# PROC051C_XDS110_Interface_1A.net
KiCad netlist of a schematic drawn in Altium Designer
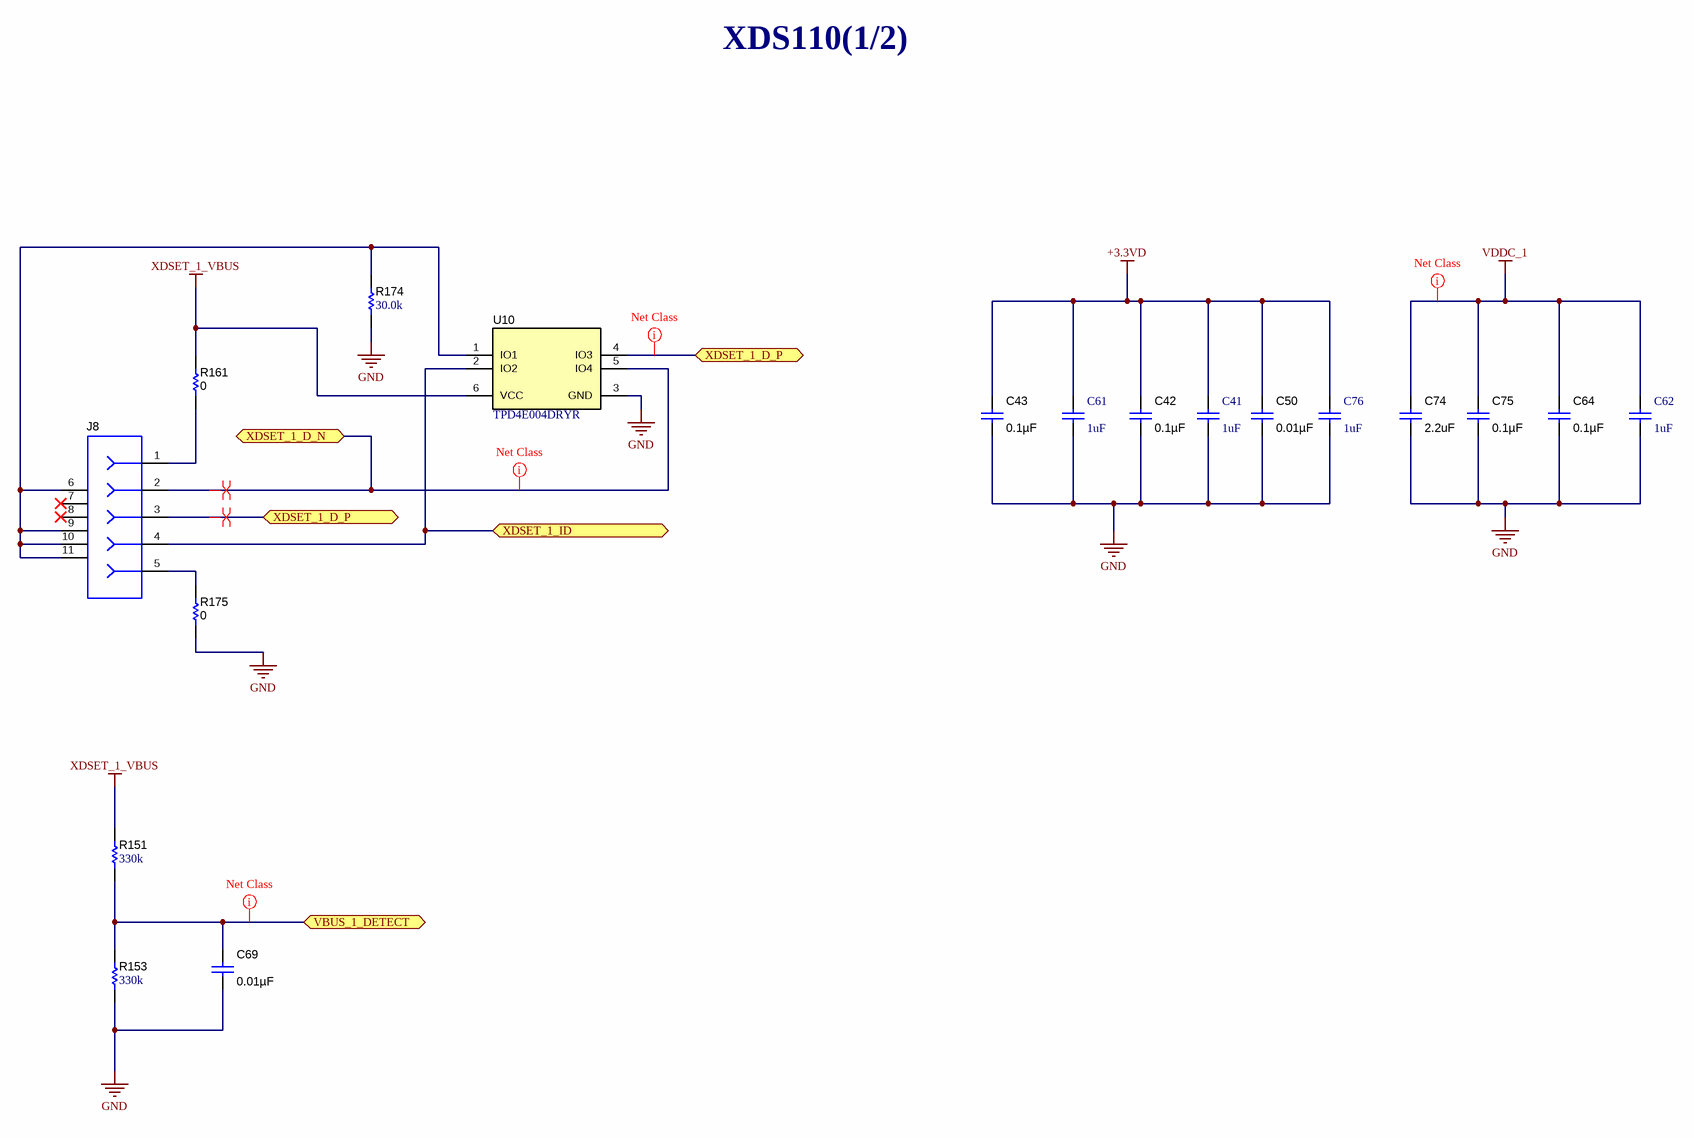
[diagram p0: PROC051C_XDS110 Interface_1A.SchDoc]

(export (version "E")
  (design (tool "Eeschema 10.0.6"))
  (components
    (comp (ref "C41")
      (value "GCM155C71A105KE38D")
      (footprint "0402_070")
      (description "CAP, CERM, 1 uF, 10 V, +/- 10%, X7S, AEC-Q200 Grade 1, 0402")
      (fields
        (field (name "MANUFACTURER") "MuRata")
        (field (name "VALUEDISPLAYED") "1uF")
        (field (name "PUBLISHER") "Texas Instruments")
      )
      (libsource (lib "Altium Vault - TI") (part "CMP-0006349-2"))
    )
    (comp (ref "C42")
      (value "C0402C104K8RACTU")
      (footprint "0402L")
      (description "CAP, CERM, 0.1 µF, 10 V,+/- 10%, X7R, 0402")
      (fields (field (name "MANUFACTURER") "Kemet") (field (name "VALUEDISPLAYED") "0.1µF"))
      (libsource (lib "Altium Vault - TI") (part "Capacitor"))
    )
    (comp (ref "C43")
      (value "C0402C104K8RACTU")
      (footprint "0402L")
      (description "CAP, CERM, 0.1 µF, 10 V,+/- 10%, X7R, 0402")
      (fields (field (name "MANUFACTURER") "Kemet") (field (name "VALUEDISPLAYED") "0.1µF"))
      (libsource (lib "Altium Vault - TI") (part "Capacitor"))
    )
    (comp (ref "C50")
      (value "C0402C103K4RACTU")
      (footprint "0402L")
      (description "CAP, CERM, 0.01 µF, 16 V,+/- 10%, X7R, 0402")
      (fields (field (name "MANUFACTURER") "Kemet") (field (name "VALUEDISPLAYED") "0.01µF"))
      (libsource (lib "Altium Vault - TI") (part "Capacitor"))
    )
    (comp (ref "C61")
      (value "GCM155C71A105KE38D")
      (footprint "0402_070")
      (description "CAP, CERM, 1 uF, 10 V, +/- 10%, X7S, AEC-Q200 Grade 1, 0402")
      (fields
        (field (name "MANUFACTURER") "MuRata")
        (field (name "VALUEDISPLAYED") "1uF")
        (field (name "PUBLISHER") "Texas Instruments")
      )
      (libsource (lib "Altium Vault - TI") (part "CMP-0006349-2"))
    )
    (comp (ref "C62")
      (value "GCM155C71A105KE38D")
      (footprint "0402_070")
      (description "CAP, CERM, 1 uF, 10 V, +/- 10%, X7S, AEC-Q200 Grade 1, 0402")
      (fields
        (field (name "MANUFACTURER") "MuRata")
        (field (name "VALUEDISPLAYED") "1uF")
        (field (name "PUBLISHER") "Texas Instruments")
      )
      (libsource (lib "Altium Vault - TI") (part "CMP-0006349-2"))
    )
    (comp (ref "C64")
      (value "C0402C104K8RACTU")
      (footprint "0402L")
      (description "CAP, CERM, 0.1 µF, 10 V,+/- 10%, X7R, 0402")
      (fields (field (name "MANUFACTURER") "Kemet") (field (name "VALUEDISPLAYED") "0.1µF"))
      (libsource (lib "Altium Vault - TI") (part "Capacitor"))
    )
    (comp (ref "C69")
      (value "C0402C103K4RACTU")
      (footprint "0402L")
      (description "CAP, CERM, 0.01 µF, 16 V,+/- 10%, X7R, 0402")
      (fields (field (name "MANUFACTURER") "Kemet") (field (name "VALUEDISPLAYED") "0.01µF"))
      (libsource (lib "Altium Vault - TI") (part "Capacitor"))
    )
    (comp (ref "C74")
      (value "C1005X7S1A225K050BC")
      (footprint "0402_065L")
      (description "CAP, CERM, 2.2 uF, 10 V, +/- 10%, X7S, 0402")
      (fields
        (field (name "MANUFACTURER") "TDK")
        (field (name "VALUEDISPLAYED") "2.2uF")
        (field (name "PUBLISHER") "Texas Instruments")
      )
      (libsource (lib "Altium Vault - TI") (part "CMP-0006302-2"))
    )
    (comp (ref "C75")
      (value "C0402C104K8RACTU")
      (footprint "0402L")
      (description "CAP, CERM, 0.1 µF, 10 V,+/- 10%, X7R, 0402")
      (fields (field (name "MANUFACTURER") "Kemet") (field (name "VALUEDISPLAYED") "0.1µF"))
      (libsource (lib "Altium Vault - TI") (part "Capacitor"))
    )
    (comp (ref "C76")
      (value "GCM155C71A105KE38D")
      (footprint "0402_070")
      (description "CAP, CERM, 1 uF, 10 V, +/- 10%, X7S, AEC-Q200 Grade 1, 0402")
      (fields
        (field (name "MANUFACTURER") "MuRata")
        (field (name "VALUEDISPLAYED") "1uF")
        (field (name "PUBLISHER") "Texas Instruments")
      )
      (libsource (lib "Altium Vault - TI") (part "CMP-0006349-2"))
    )
    (comp (ref "J8")
      (value "105017-0001")
      (footprint "CONN_105017-0001")
      (description "Connector, Receptacle, Micro-USB Type B, R/A, Bottom Mount SMT")
      (fields (field (name "MANUFACTURER") "Molex") (field (name "PUBLISHER") "Texas Instruments"))
      (libsource (lib "Altium Vault - TI") (part "CONN_105017-0001"))
    )
    (comp (ref "R151")
      (value "CRCW0402330KFKED")
      (footprint "0402L")
      (description "RES, 330 k, 1%, 0.063 W, AEC-Q200 Grade 0, 0402")
      (fields (field (name "MANUFACTURER") "Vishay-Dale") (field (name "VALUEDISPLAYED") "330k"))
      (libsource (lib "Altium Vault - TI") (part "Resistor"))
    )
    (comp (ref "R153")
      (value "CRCW0402330KFKED")
      (footprint "0402L")
      (description "RES, 330 k, 1%, 0.063 W, AEC-Q200 Grade 0, 0402")
      (fields (field (name "MANUFACTURER") "Vishay-Dale") (field (name "VALUEDISPLAYED") "330k"))
      (libsource (lib "Altium Vault - TI") (part "Resistor"))
    )
    (comp (ref "R161")
      (value "MCT06030Z0000ZP500")
      (footprint "0603")
      (description "RES, 0, 5%, 0.125 W, 0603")
      (fields
        (field (name "MANUFACTURER") "Vishay/Beyschlag")
        (field (name "VALUEDISPLAYED") "0")
        (field (name "PUBLISHER") "Texas Instruments")
      )
      (libsource (lib "Altium Vault - TI") (part "Resistor"))
    )
    (comp (ref "R174")
      (value "CRCW040230K0FKED")
      (footprint "0402L")
      (description "RES, 30.0 k, 1%, 0.063 W, AEC-Q200 Grade 0, 0402")
      (fields (field (name "MANUFACTURER") "Vishay-Dale") (field (name "VALUEDISPLAYED") "30.0k"))
      (libsource (lib "Altium Vault - TI") (part "Resistor"))
    )
    (comp (ref "R175")
      (value "MCT06030Z0000ZP500")
      (footprint "0603")
      (description "RES, 0, 5%, 0.125 W, 0603")
      (fields
        (field (name "MANUFACTURER") "Vishay/Beyschlag")
        (field (name "VALUEDISPLAYED") "0")
        (field (name "PUBLISHER") "Texas Instruments")
      )
      (libsource (lib "Altium Vault - TI") (part "Resistor"))
    )
    (comp (ref "U10")
      (value "TPD4E004DRYR")
      (footprint "DRY0006A")
      (description "4-Channel ESD Protection Array for High-Speed Data Interfaces, DRY0006A (USON-6)")
      (fields (field (name "MANUFACTURER") "Texas Instruments") (field (name "PARTNUMBER") "TPD4E004DRYR"))
      (libsource (lib "Altium Vault - TI") (part "TI-TPD4E004-SON_DRY-6"))
    )
  )
  (nets
    (net (code "1") (name "+3.3VD") (class "Default")
      (node (ref "C41") (pin "1") (pinfunction "1_1") (pintype "passive"))
      (node (ref "C42") (pin "2") (pinfunction "2_2") (pintype "passive"))
      (node (ref "C43") (pin "2") (pinfunction "2_2") (pintype "passive"))
      (node (ref "C50") (pin "2") (pinfunction "2_2") (pintype "passive"))
      (node (ref "C61") (pin "1") (pinfunction "1_1") (pintype "passive"))
      (node (ref "C76") (pin "1") (pinfunction "1_1") (pintype "passive"))
    )
    (net (code "2") (name "/VBUS_1_DETECT") (class "Default")
      (node (ref "C69") (pin "2") (pinfunction "2_2") (pintype "passive"))
      (node (ref "R151") (pin "1") (pinfunction "1_1") (pintype "passive"))
      (node (ref "R153") (pin "2") (pinfunction "2_2") (pintype "passive"))
    )
    (net (code "3") (name "/XDSET_1_D_N") (class "Default")
      (node (ref "J8") (pin "2") (pintype "passive"))
      (node (ref "U10") (pin "5") (pinfunction "IO4_5") (pintype "passive"))
    )
    (net (code "4") (name "/XDSET_1_D_P") (class "Default")
      (node (ref "J8") (pin "3") (pintype "passive"))
      (node (ref "U10") (pin "4") (pinfunction "IO3_4") (pintype "passive"))
    )
    (net (code "5") (name "/XDSET_1_ID") (class "Default")
      (node (ref "J8") (pin "4") (pintype "passive"))
      (node (ref "U10") (pin "2") (pinfunction "IO2_2") (pintype "passive"))
    )
    (net (code "6") (name "GND") (class "Default")
      (node (ref "C41") (pin "2") (pinfunction "2_2") (pintype "passive"))
      (node (ref "C42") (pin "1") (pinfunction "1_1") (pintype "passive"))
      (node (ref "C43") (pin "1") (pinfunction "1_1") (pintype "passive"))
      (node (ref "C50") (pin "1") (pinfunction "1_1") (pintype "passive"))
      (node (ref "C61") (pin "2") (pinfunction "2_2") (pintype "passive"))
      (node (ref "C62") (pin "2") (pinfunction "2_2") (pintype "passive"))
      (node (ref "C64") (pin "1") (pinfunction "1_1") (pintype "passive"))
      (node (ref "C69") (pin "1") (pinfunction "1_1") (pintype "passive"))
      (node (ref "C74") (pin "1") (pinfunction "1_1") (pintype "passive"))
      (node (ref "C75") (pin "1") (pinfunction "1_1") (pintype "passive"))
      (node (ref "C76") (pin "2") (pinfunction "2_2") (pintype "passive"))
      (node (ref "R153") (pin "1") (pinfunction "1_1") (pintype "passive"))
      (node (ref "R174") (pin "1") (pinfunction "1_1") (pintype "passive"))
      (node (ref "R175") (pin "1") (pinfunction "1_1") (pintype "passive"))
      (node (ref "U10") (pin "3") (pinfunction "GND_3") (pintype "power_in"))
    )
    (net (code "7") (name "Net-(J8-Pad1)") (class "Default")
      (node (ref "J8") (pin "1") (pintype "passive"))
      (node (ref "R161") (pin "1") (pinfunction "1_1") (pintype "passive"))
    )
    (net (code "8") (name "Net-(J8-Pad5)") (class "Default")
      (node (ref "J8") (pin "5") (pintype "passive"))
      (node (ref "R175") (pin "2") (pinfunction "2_2") (pintype "passive"))
    )
    (net (code "9") (name "Net-(U10-IO1)") (class "Default")
      (node (ref "J8") (pin "10") (pintype "passive"))
      (node (ref "J8") (pin "11") (pintype "passive"))
      (node (ref "J8") (pin "6") (pintype "passive"))
      (node (ref "J8") (pin "9") (pintype "passive"))
      (node (ref "R174") (pin "2") (pinfunction "2_2") (pintype "passive"))
      (node (ref "U10") (pin "1") (pinfunction "IO1_1") (pintype "passive"))
    )
    (net (code "10") (name "VDDC_1") (class "Default")
      (node (ref "C62") (pin "1") (pinfunction "1_1") (pintype "passive"))
      (node (ref "C64") (pin "2") (pinfunction "2_2") (pintype "passive"))
      (node (ref "C74") (pin "2") (pinfunction "2_2") (pintype "passive"))
      (node (ref "C75") (pin "2") (pinfunction "2_2") (pintype "passive"))
    )
    (net (code "11") (name "XDSET_1_VBUS") (class "Default")
      (node (ref "R151") (pin "2") (pinfunction "2_2") (pintype "passive"))
      (node (ref "R161") (pin "2") (pinfunction "2_2") (pintype "passive"))
      (node (ref "U10") (pin "6") (pinfunction "VCC_6") (pintype "power_in"))
    )
    (net (code "12") (name "unconnected-(J8-Pad7)") (class "Default")
      (node (ref "J8") (pin "7") (pintype "passive+no_connect"))
    )
    (net (code "13") (name "unconnected-(J8-Pad8)") (class "Default")
      (node (ref "J8") (pin "8") (pintype "passive+no_connect"))
    )
  )
)
